# BEI_Kimco_Magnetic_Cylindrical_Frameless.net
KiCad netlist of a schematic drawn in EasyEDA Pro
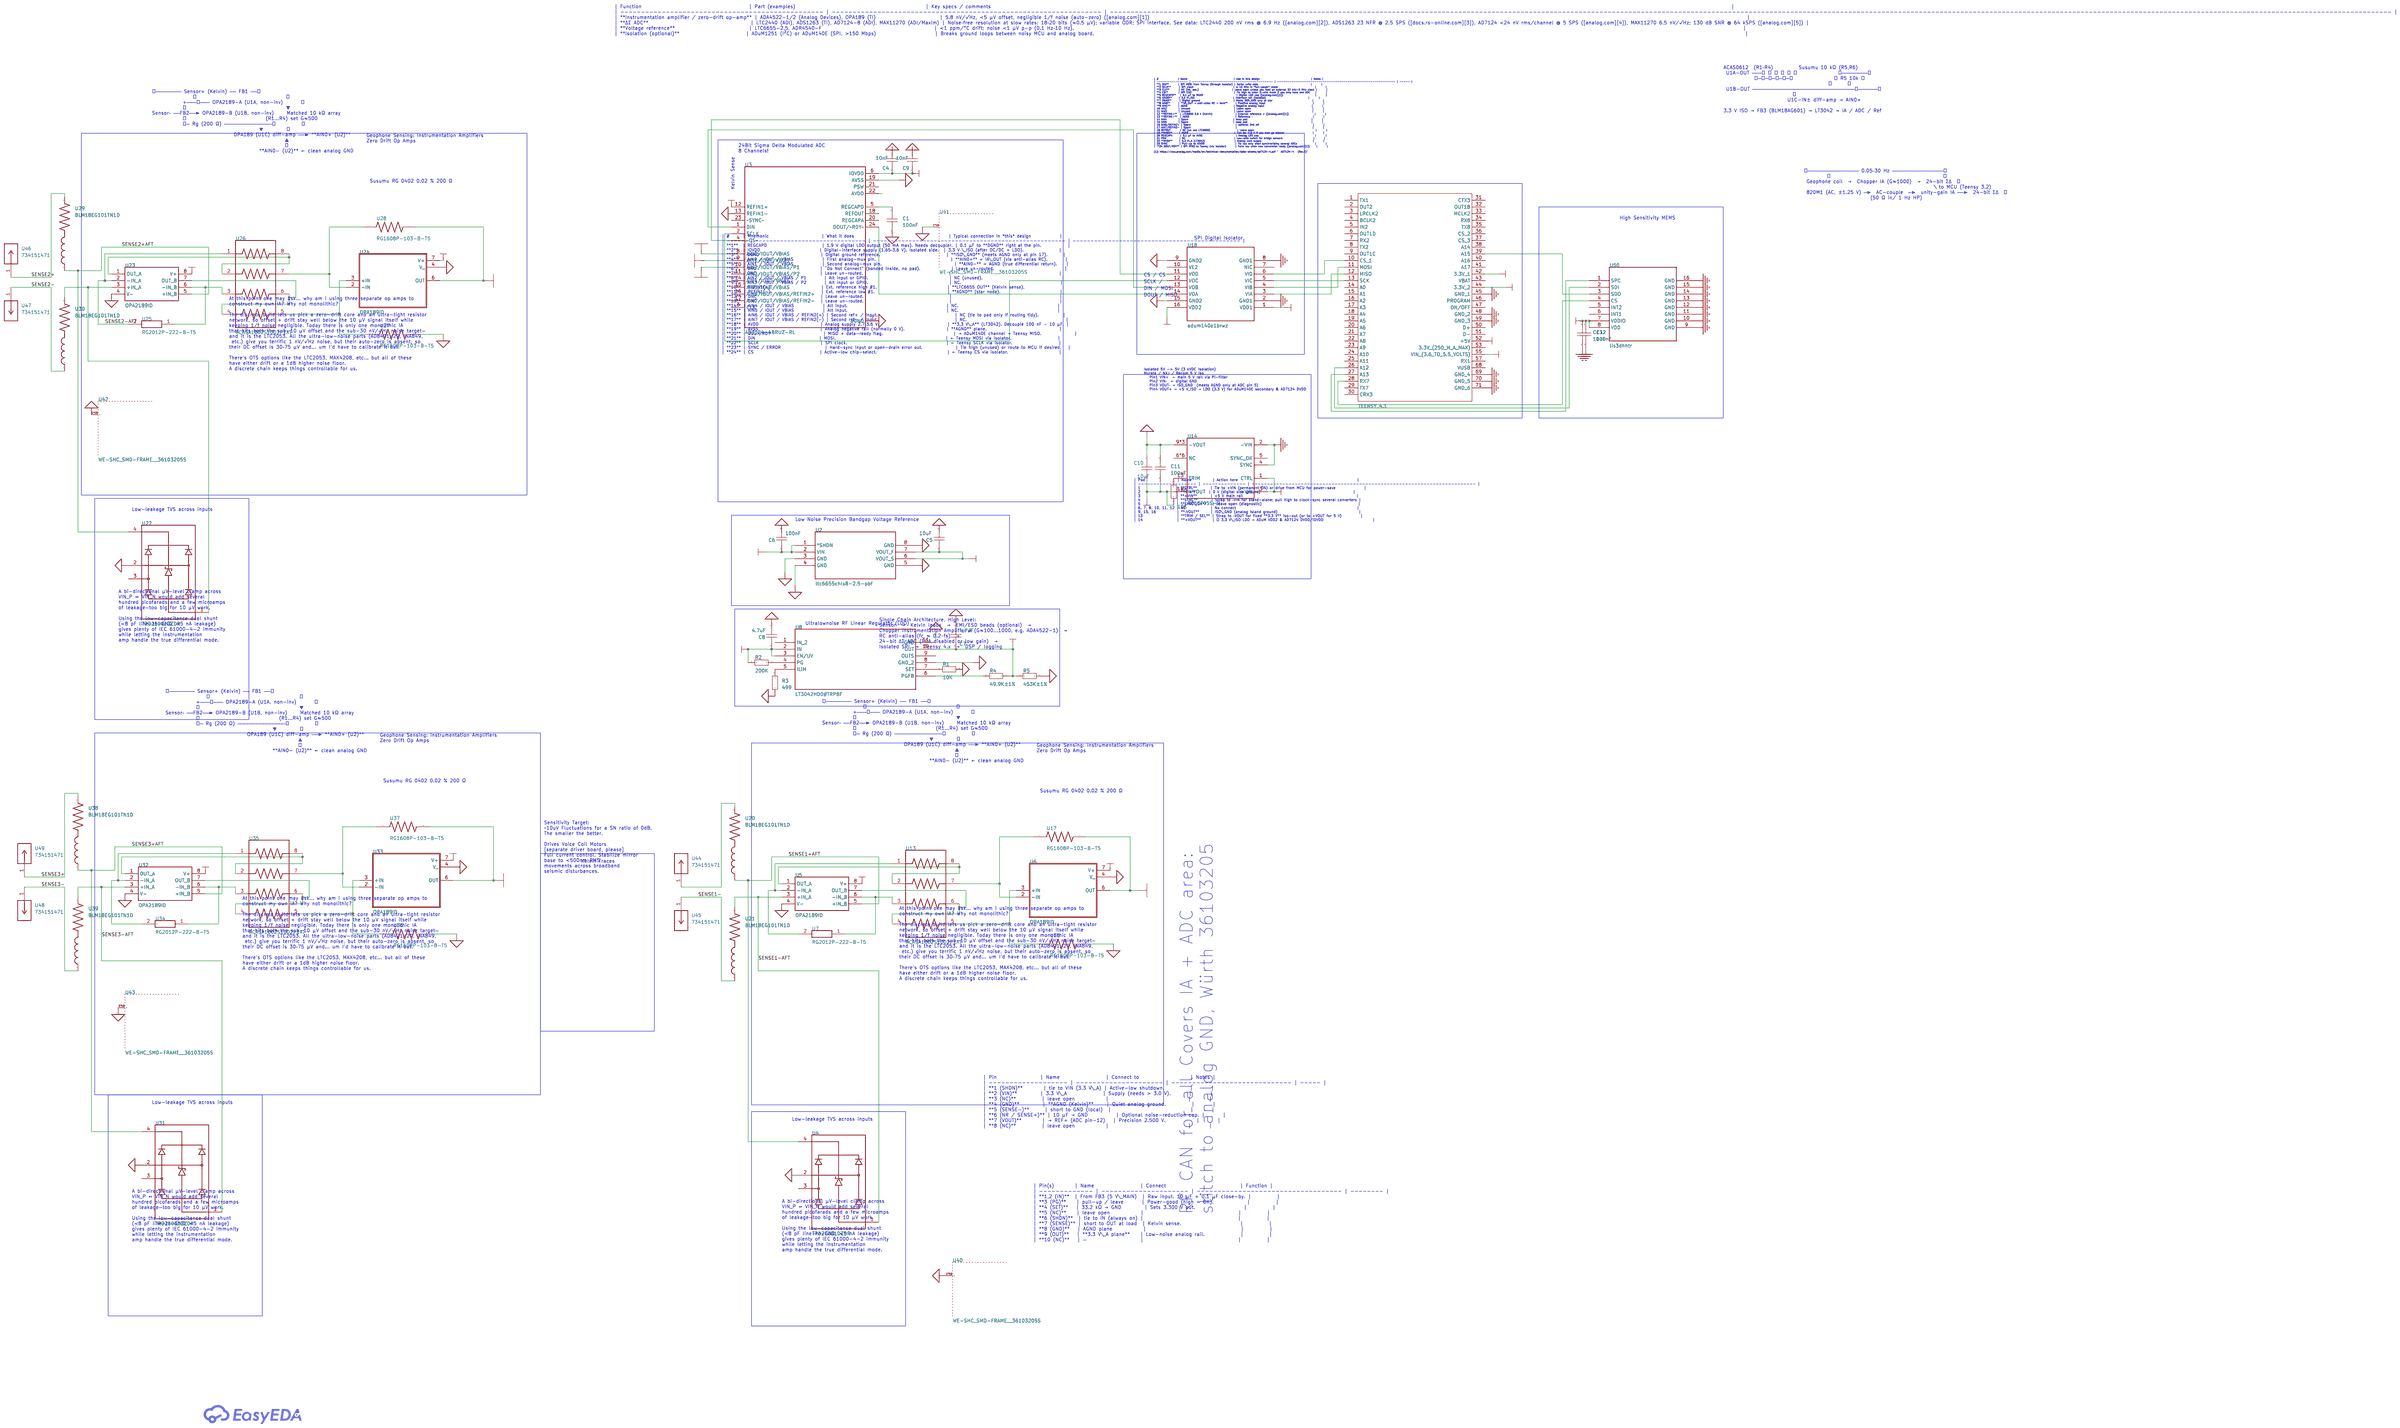
[diagram p0: schematic sheet]

(export (version "E")
  (design (tool "Eeschema 10.0.6"))
  (components
    (comp (ref "C1")
      (value "100nF")
      (footprint "easyedapro:C0603")
      (libsource (lib "easyedapro") (part "CapAcitance"))
    )
    (comp (ref "C4")
      (value "10nF")
      (footprint "easyedapro:C0603")
      (libsource (lib "easyedapro") (part "CapAcitance"))
    )
    (comp (ref "C5")
      (value "10uF")
      (footprint "easyedapro:C0603")
      (libsource (lib "easyedapro") (part "CapAcitance"))
    )
    (comp (ref "C6")
      (value "100nF")
      (footprint "easyedapro:C0603")
      (libsource (lib "easyedapro") (part "CapAcitance"))
    )
    (comp (ref "C7")
      (value "4.7uF")
      (footprint "easyedapro:C0603")
      (libsource (lib "easyedapro") (part "CapAcitance"))
    )
    (comp (ref "C8")
      (value "4.7uF")
      (footprint "easyedapro:C0603")
      (libsource (lib "easyedapro") (part "CapAcitance"))
    )
    (comp (ref "C9")
      (value "10nF")
      (footprint "easyedapro:C0603")
      (libsource (lib "easyedapro") (part "CapAcitance"))
    )
    (comp (ref "C10")
      (value "10uF")
      (footprint "easyedapro:C0603")
      (libsource (lib "easyedapro") (part "CapAcitance"))
    )
    (comp (ref "C11")
      (value "100nF")
      (footprint "easyedapro:C0603")
      (libsource (lib "easyedapro") (part "CapAcitance"))
    )
    (comp (ref "C12")
      (value "100nF")
      (footprint "easyedapro:C0603")
      (libsource (lib "easyedapro") (part "CapAcitance"))
    )
    (comp (ref "C13")
      (value "10uF")
      (footprint "easyedapro:C0603")
      (libsource (lib "easyedapro") (part "CapAcitance"))
    )
    (comp (ref "R1") (value "10K") (footprint "easyedapro:R0603") (libsource (lib "easyedapro") (part "电阻")))
    (comp (ref "R2") (value "200K") (footprint "easyedapro:R0603") (libsource (lib "easyedapro") (part "电阻")))
    (comp (ref "R3") (value "499") (footprint "easyedapro:R0603") (libsource (lib "easyedapro") (part "电阻")))
    (comp (ref "R4")
      (value "49.9K±1%")
      (footprint "easyedapro:R0603")
      (libsource (lib "easyedapro") (part "电阻"))
    )
    (comp (ref "R5")
      (value "453K±1%")
      (footprint "easyedapro:R0603")
      (libsource (lib "easyedapro") (part "电阻"))
    )
    (comp (ref "R6") (value "10K") (footprint "easyedapro:R0603") (libsource (lib "easyedapro") (part "电阻")))
    (comp (ref "U2")
      (value "ltc6655chls8-2.5-pbf")
      (footprint "easyedapro:LTC6655CHLS8-2.5-PBF")
      (libsource (lib "easyedapro") (part "ltc6655chls8-2.5-pbf"))
    )
    (comp (ref "U3")
      (value "AD7124-4BRUZ-RL")
      (footprint "easyedapro:SOP65P640X120-24N")
      (libsource (lib "easyedapro") (part "AD7124-4BRUZ-RL"))
    )
    (comp (ref "U4")
      (value "TPD2E001DZDR")
      (footprint "easyedapro:SOT192P237X122-4N")
      (libsource (lib "easyedapro") (part "TPD2E001DZDR"))
    )
    (comp (ref "U5")
      (value "OPA2189ID")
      (footprint "easyedapro:SOIC127P600X175-8N")
      (description "2 Op Amps in 1. Zero Drift.")
      (libsource (lib "easyedapro") (part "OPA2189ID"))
    )
    (comp (ref "U6")
      (value "OPA189ID")
      (footprint "easyedapro:SOIC127P599X175-8N")
      (libsource (lib "easyedapro") (part "OPA189ID"))
    )
    (comp (ref "U7")
      (value "RG2012P-222-B-T5")
      (footprint "easyedapro:RESC2012X50N")
      (libsource (lib "easyedapro") (part "RG2012P-222-B-T5"))
    )
    (comp (ref "U8")
      (value "LT3042HDD#TRPBF")
      (footprint "easyedapro:DFN-10_DD")
      (description "LDO")
      (libsource (lib "easyedapro") (part "LT3042HDD#TRPBF"))
    )
    (comp (ref "U13")
      (value "ACASA1002S1002P1AT")
      (footprint "easyedapro:RESCAXS80P320X150X55-8N")
      (libsource (lib "easyedapro") (part "ACASA1002S1002P1AT"))
    )
    (comp (ref "U14")
      (value "R05CT05S-R")
      (footprint "easyedapro:SOIC127P1030X265-16N")
      (description "Isolated 5 V→5 V DC/DC")
      (libsource (lib "easyedapro") (part "R05CT05S-R"))
    )
    (comp (ref "U16")
      (value "RG1608P-103-B-T5")
      (footprint "easyedapro:RESC1608X50N")
      (libsource (lib "easyedapro") (part "RG1608P-103-B-T5"))
    )
    (comp (ref "U17")
      (value "RG1608P-103-B-T5")
      (footprint "easyedapro:RESC1608X50N")
      (libsource (lib "easyedapro") (part "RG1608P-103-B-T5"))
    )
    (comp (ref "U18")
      (value "adum140e1brwz")
      (footprint "easyedapro:ADUM140E1BRWZ")
      (libsource (lib "easyedapro") (part "adum140e1brwz"))
    )
    (comp (ref "U20")
      (value "BLM18EG101TN1D")
      (footprint "easyedapro:BEADC1608X65N")
      (description "Ferrite Bead")
      (libsource (lib "easyedapro") (part "BLM18EG101TN1D"))
    )
    (comp (ref "U21")
      (value "BLM18EG101TN1D")
      (footprint "easyedapro:BEADC1608X65N")
      (description "Ferrite Bead")
      (libsource (lib "easyedapro") (part "BLM18EG101TN1D"))
    )
    (comp (ref "U22")
      (value "TPD2E001DZDR")
      (footprint "easyedapro:SOT192P237X122-4N")
      (libsource (lib "easyedapro") (part "TPD2E001DZDR"))
    )
    (comp (ref "U23")
      (value "OPA2189ID")
      (footprint "easyedapro:SOIC127P600X175-8N")
      (description "2 Op Amps in 1. Zero Drift.")
      (libsource (lib "easyedapro") (part "OPA2189ID"))
    )
    (comp (ref "U24")
      (value "OPA189ID")
      (footprint "easyedapro:SOIC127P599X175-8N")
      (libsource (lib "easyedapro") (part "OPA189ID"))
    )
    (comp (ref "U25")
      (value "RG2012P-222-B-T5")
      (footprint "easyedapro:RESC2012X50N")
      (libsource (lib "easyedapro") (part "RG2012P-222-B-T5"))
    )
    (comp (ref "U26")
      (value "ACASA1002S1002P1AT")
      (footprint "easyedapro:RESCAXS80P320X150X55-8N")
      (libsource (lib "easyedapro") (part "ACASA1002S1002P1AT"))
    )
    (comp (ref "U27")
      (value "RG1608P-103-B-T5")
      (footprint "easyedapro:RESC1608X50N")
      (libsource (lib "easyedapro") (part "RG1608P-103-B-T5"))
    )
    (comp (ref "U28")
      (value "RG1608P-103-B-T5")
      (footprint "easyedapro:RESC1608X50N")
      (libsource (lib "easyedapro") (part "RG1608P-103-B-T5"))
    )
    (comp (ref "U29")
      (value "BLM18EG101TN1D")
      (footprint "easyedapro:BEADC1608X65N")
      (description "Ferrite Bead")
      (libsource (lib "easyedapro") (part "BLM18EG101TN1D"))
    )
    (comp (ref "U30")
      (value "BLM18EG101TN1D")
      (footprint "easyedapro:BEADC1608X65N")
      (description "Ferrite Bead")
      (libsource (lib "easyedapro") (part "BLM18EG101TN1D"))
    )
    (comp (ref "U31")
      (value "TPD2E001DZDR")
      (footprint "easyedapro:SOT192P237X122-4N")
      (libsource (lib "easyedapro") (part "TPD2E001DZDR"))
    )
    (comp (ref "U32")
      (value "OPA2189ID")
      (footprint "easyedapro:SOIC127P600X175-8N")
      (description "2 Op Amps in 1. Zero Drift.")
      (libsource (lib "easyedapro") (part "OPA2189ID"))
    )
    (comp (ref "U33")
      (value "OPA189ID")
      (footprint "easyedapro:SOIC127P599X175-8N")
      (libsource (lib "easyedapro") (part "OPA189ID"))
    )
    (comp (ref "U34")
      (value "RG2012P-222-B-T5")
      (footprint "easyedapro:RESC2012X50N")
      (libsource (lib "easyedapro") (part "RG2012P-222-B-T5"))
    )
    (comp (ref "U35")
      (value "ACASA1002S1002P1AT")
      (footprint "easyedapro:RESCAXS80P320X150X55-8N")
      (libsource (lib "easyedapro") (part "ACASA1002S1002P1AT"))
    )
    (comp (ref "U36")
      (value "RG1608P-103-B-T5")
      (footprint "easyedapro:RESC1608X50N")
      (libsource (lib "easyedapro") (part "RG1608P-103-B-T5"))
    )
    (comp (ref "U37")
      (value "RG1608P-103-B-T5")
      (footprint "easyedapro:RESC1608X50N")
      (libsource (lib "easyedapro") (part "RG1608P-103-B-T5"))
    )
    (comp (ref "U38")
      (value "BLM18EG101TN1D")
      (footprint "easyedapro:BEADC1608X65N")
      (description "Ferrite Bead")
      (libsource (lib "easyedapro") (part "BLM18EG101TN1D"))
    )
    (comp (ref "U39")
      (value "BLM18EG101TN1D")
      (footprint "easyedapro:BEADC1608X65N")
      (description "Ferrite Bead")
      (libsource (lib "easyedapro") (part "BLM18EG101TN1D"))
    )
    (comp (ref "U40")
      (value "WE-SHC_SMD-FRAME__36103205S")
      (footprint "easyedapro:WE-SHC_SMD-FRAME_36103205S")
      (libsource (lib "easyedapro") (part "WE-SHC_SMD-FRAME__36103205S"))
    )
    (comp (ref "U41")
      (value "WE-SHC_SMD-FRAME__36103205S")
      (footprint "easyedapro:WE-SHC_SMD-FRAME_36103205S")
      (libsource (lib "easyedapro") (part "WE-SHC_SMD-FRAME__36103205S"))
    )
    (comp (ref "U42")
      (value "WE-SHC_SMD-FRAME__36103205S")
      (footprint "easyedapro:WE-SHC_SMD-FRAME_36103205S")
      (libsource (lib "easyedapro") (part "WE-SHC_SMD-FRAME__36103205S"))
    )
    (comp (ref "U43")
      (value "WE-SHC_SMD-FRAME__36103205S")
      (footprint "easyedapro:WE-SHC_SMD-FRAME_36103205S")
      (libsource (lib "easyedapro") (part "WE-SHC_SMD-FRAME__36103205S"))
    )
    (comp (ref "U44")
      (value "734151471")
      (footprint "easyedapro:CONN_734151471_MOL")
      (libsource (lib "easyedapro") (part "734151471"))
    )
    (comp (ref "U45")
      (value "734151471")
      (footprint "easyedapro:CONN_734151471_MOL")
      (libsource (lib "easyedapro") (part "734151471"))
    )
    (comp (ref "U46")
      (value "734151471")
      (footprint "easyedapro:CONN_734151471_MOL")
      (libsource (lib "easyedapro") (part "734151471"))
    )
    (comp (ref "U47")
      (value "734151471")
      (footprint "easyedapro:CONN_734151471_MOL")
      (libsource (lib "easyedapro") (part "734151471"))
    )
    (comp (ref "U48")
      (value "734151471")
      (footprint "easyedapro:CONN_734151471_MOL")
      (libsource (lib "easyedapro") (part "734151471"))
    )
    (comp (ref "U49")
      (value "734151471")
      (footprint "easyedapro:CONN_734151471_MOL")
      (libsource (lib "easyedapro") (part "734151471"))
    )
    (comp (ref "U50")
      (value "lis3dhhtr")
      (footprint "easyedapro:LIS3DHHTR")
      (libsource (lib "easyedapro") (part "lis3dhhtr"))
    )
    (comp (ref "U51")
      (value "TEENSY_4.1")
      (footprint "easyedapro:TEENSY41")
      (libsource (lib "easyedapro") (part "TEENSY_4.1"))
    )
  )
  (nets
    (net (code "1") (name "+2.5V") (class "Default")
      (node (ref "C5") (pin "2") (pinfunction "2_2") (pintype "input"))
      (node (ref "U2") (pin "6") (pinfunction "VOUT_S_6") (pintype "unspecified"))
      (node (ref "U2") (pin "7") (pinfunction "VOUT_F_7") (pintype "unspecified"))
      (node (ref "U3") (pin "12") (pinfunction "REFIN1+_12") (pintype "input"))
    )
    (net (code "2") (name "+3.3VANALOGSIDE") (class "Default")
      (node (ref "C4") (pin "1") (pinfunction "1_1") (pintype "input"))
      (node (ref "C6") (pin "2") (pinfunction "2_2") (pintype "input"))
      (node (ref "C7") (pin "2") (pinfunction "2_2") (pintype "input"))
      (node (ref "C9") (pin "1") (pinfunction "1_1") (pintype "input"))
      (node (ref "R4") (pin "2") (pinfunction "2_2") (pintype "input"))
      (node (ref "R5") (pin "1") (pinfunction "1_1") (pintype "input"))
      (node (ref "U18") (pin "16") (pinfunction "VDD2_16") (pintype "unspecified"))
      (node (ref "U2") (pin "1") (pinfunction "*SHDN_1") (pintype "unspecified"))
      (node (ref "U2") (pin "2") (pinfunction "VIN_2") (pintype "unspecified"))
      (node (ref "U23") (pin "8") (pinfunction "V+_8") (pintype "bidirectional"))
      (node (ref "U24") (pin "7") (pinfunction "V+_7") (pintype "unspecified"))
      (node (ref "U3") (pin "6") (pinfunction "IOVDD_6") (pintype "unspecified"))
      (node (ref "U32") (pin "8") (pinfunction "V+_8") (pintype "bidirectional"))
      (node (ref "U33") (pin "7") (pinfunction "V+_7") (pintype "unspecified"))
      (node (ref "U5") (pin "8") (pinfunction "V+_8") (pintype "bidirectional"))
      (node (ref "U6") (pin "7") (pinfunction "V+_7") (pintype "unspecified"))
      (node (ref "U8") (pin "10") (pinfunction "OUT_10") (pintype "output"))
    )
    (net (code "3") (name "+3.3V_D") (class "Default")
      (node (ref "C12") (pin "2") (pinfunction "2_2") (pintype "input"))
      (node (ref "C13") (pin "2") (pinfunction "2_2") (pintype "input"))
      (node (ref "U18") (pin "1") (pinfunction "VDD1_1") (pintype "unspecified"))
      (node (ref "U50") (pin "7") (pinfunction "VDDIO_7") (pintype "unspecified"))
      (node (ref "U50") (pin "8") (pinfunction "VDD_8") (pintype "unspecified"))
      (node (ref "U51") (pin "42") (pinfunction "3.3V_1_42") (pintype "bidirectional"))
      (node (ref "U51") (pin "44") (pinfunction "3.3V_2_44") (pintype "bidirectional"))
    )
    (net (code "4") (name "+5V_D") (class "Default")
      (node (ref "U14") (pin "1") (pinfunction "CTRL_1") (pintype "input"))
      (node (ref "U14") (pin "3") (pinfunction "+VIN_3") (pintype "input"))
      (node (ref "U51") (pin "52") (pinfunction "+5V_52") (pintype "bidirectional"))
      (node (ref "U51") (pin "55") (pinfunction "VIN_(3.6_TO_5.5_VOLTS)_55") (pintype "bidirectional"))
    )
    (net (code "5") (name "+5V_ISO") (class "Default")
      (node (ref "C10") (pin "1") (pinfunction "1_1") (pintype "input"))
      (node (ref "C11") (pin "1") (pinfunction "1_1") (pintype "input"))
      (node (ref "C8") (pin "2") (pinfunction "2_2") (pintype "input"))
      (node (ref "R2") (pin "1") (pinfunction "1_1") (pintype "input"))
      (node (ref "R6") (pin "1") (pinfunction "1_1") (pintype "input"))
      (node (ref "U14") (pin "14") (pinfunction "+VOUT_14") (pintype "output"))
      (node (ref "U8") (pin "2") (pinfunction "IN_2") (pintype "input"))
      (node (ref "U8") (pin "3") (pinfunction "EN/UV_3") (pintype "output"))
    )
    (net (code "6") (name "/SENSE1+AFT") (class "Default")
      (node (ref "U20") (pin "1") (pinfunction "1_1") (pintype "unspecified"))
      (node (ref "U4") (pin "4") (pinfunction "VCC_4") (pintype "unspecified"))
      (node (ref "U5") (pin "5") (pinfunction "+IN_B_5") (pintype "bidirectional"))
    )
    (net (code "7") (name "/SENSE1-") (class "Default")
      (node (ref "U21") (pin "1") (pinfunction "1_1") (pintype "unspecified"))
      (node (ref "U45") (pin "1") (pinfunction "1_1") (pintype "unspecified"))
    )
    (net (code "8") (name "/SENSE1-AFT") (class "Default")
      (node (ref "U21") (pin "2") (pinfunction "2_2") (pintype "unspecified"))
      (node (ref "U4") (pin "1") (pinfunction "GND_1") (pintype "unspecified"))
      (node (ref "U5") (pin "3") (pinfunction "+IN_A_3") (pintype "bidirectional"))
    )
    (net (code "9") (name "/SENSE2+") (class "Default")
      (node (ref "U29") (pin "2") (pinfunction "2_2") (pintype "unspecified"))
      (node (ref "U46") (pin "1") (pinfunction "1_1") (pintype "unspecified"))
    )
    (net (code "10") (name "/SENSE2+AFT") (class "Default")
      (node (ref "U22") (pin "4") (pinfunction "VCC_4") (pintype "unspecified"))
      (node (ref "U23") (pin "5") (pinfunction "+IN_B_5") (pintype "bidirectional"))
      (node (ref "U29") (pin "1") (pinfunction "1_1") (pintype "unspecified"))
    )
    (net (code "11") (name "/SENSE2-") (class "Default")
      (node (ref "U30") (pin "1") (pinfunction "1_1") (pintype "unspecified"))
      (node (ref "U47") (pin "1") (pinfunction "1_1") (pintype "unspecified"))
    )
    (net (code "12") (name "/SENSE2-AFT") (class "Default")
      (node (ref "U23") (pin "2") (pinfunction "-IN_A_2") (pintype "bidirectional"))
      (node (ref "U25") (pin "2") (pinfunction "2_2") (pintype "bidirectional"))
      (node (ref "U26") (pin "1") (pinfunction "1_1") (pintype "unspecified"))
    )
    (net (code "13") (name "/SENSE3+") (class "Default")
      (node (ref "U38") (pin "2") (pinfunction "2_2") (pintype "unspecified"))
      (node (ref "U49") (pin "1") (pinfunction "1_1") (pintype "unspecified"))
    )
    (net (code "14") (name "/SENSE3+AFT") (class "Default")
      (node (ref "U31") (pin "4") (pinfunction "VCC_4") (pintype "unspecified"))
      (node (ref "U32") (pin "5") (pinfunction "+IN_B_5") (pintype "bidirectional"))
      (node (ref "U38") (pin "1") (pinfunction "1_1") (pintype "unspecified"))
    )
    (net (code "15") (name "/SENSE3-") (class "Default")
      (node (ref "U39") (pin "1") (pinfunction "1_1") (pintype "unspecified"))
      (node (ref "U48") (pin "1") (pinfunction "1_1") (pintype "unspecified"))
    )
    (net (code "16") (name "/SENSE3-AFT") (class "Default")
      (node (ref "U31") (pin "1") (pinfunction "GND_1") (pintype "unspecified"))
      (node (ref "U32") (pin "3") (pinfunction "+IN_A_3") (pintype "bidirectional"))
      (node (ref "U39") (pin "2") (pinfunction "2_2") (pintype "unspecified"))
    )
    (net (code "17") (name "AGND") (class "Default")
      (node (ref "C1") (pin "2") (pinfunction "2_2") (pintype "input"))
      (node (ref "C10") (pin "2") (pinfunction "2_2") (pintype "input"))
      (node (ref "C11") (pin "2") (pinfunction "2_2") (pintype "input"))
      (node (ref "C4") (pin "2") (pinfunction "2_2") (pintype "input"))
      (node (ref "C5") (pin "1") (pinfunction "1_1") (pintype "input"))
      (node (ref "C6") (pin "1") (pinfunction "1_1") (pintype "input"))
      (node (ref "C7") (pin "1") (pinfunction "1_1") (pintype "input"))
      (node (ref "C8") (pin "1") (pinfunction "1_1") (pintype "input"))
      (node (ref "C9") (pin "2") (pinfunction "2_2") (pintype "input"))
      (node (ref "R1") (pin "2") (pinfunction "2_2") (pintype "input"))
      (node (ref "R3") (pin "1") (pinfunction "1_1") (pintype "input"))
      (node (ref "R5") (pin "2") (pinfunction "2_2") (pintype "input"))
      (node (ref "U14") (pin "9*3") (pinfunction "-VOUT_9*3") (pintype "output"))
      (node (ref "U16") (pin "2") (pinfunction "2_2") (pintype "unspecified"))
      (node (ref "U18") (pin "15") (pinfunction "GND2_15") (pintype "unspecified"))
      (node (ref "U18") (pin "9") (pinfunction "GND2_9") (pintype "unspecified"))
      (node (ref "U2") (pin "3") (pinfunction "GND_3") (pintype "unspecified"))
      (node (ref "U2") (pin "4") (pinfunction "GND_4") (pintype "unspecified"))
      (node (ref "U2") (pin "5") (pinfunction "GND_5") (pintype "unspecified"))
      (node (ref "U2") (pin "8") (pinfunction "GND_8") (pintype "unspecified"))
      (node (ref "U22") (pin "2") (pinfunction "IO1_2") (pintype "bidirectional"))
      (node (ref "U23") (pin "4") (pinfunction "V-_4") (pintype "bidirectional"))
      (node (ref "U24") (pin "4") (pinfunction "V__4") (pintype "unspecified"))
      (node (ref "U27") (pin "2") (pinfunction "2_2") (pintype "unspecified"))
      (node (ref "U3") (pin "13") (pinfunction "REFIN1-_13") (pintype "input"))
      (node (ref "U3") (pin "19") (pinfunction "AVSS_19") (pintype "unspecified"))
      (node (ref "U3") (pin "7") (pinfunction "DGND_7") (pintype "unspecified"))
      (node (ref "U31") (pin "2") (pinfunction "IO1_2") (pintype "bidirectional"))
      (node (ref "U32") (pin "4") (pinfunction "V-_4") (pintype "bidirectional"))
      (node (ref "U33") (pin "4") (pinfunction "V__4") (pintype "unspecified"))
      (node (ref "U36") (pin "2") (pinfunction "2_2") (pintype "unspecified"))
      (node (ref "U4") (pin "2") (pinfunction "IO1_2") (pintype "bidirectional"))
      (node (ref "U40") (pin "1*16") (pinfunction "GND_1*16") (pintype "unspecified"))
      (node (ref "U41") (pin "1*16") (pinfunction "GND_1*16") (pintype "unspecified"))
      (node (ref "U42") (pin "1*16") (pinfunction "GND_1*16") (pintype "unspecified"))
      (node (ref "U43") (pin "1*16") (pinfunction "GND_1*16") (pintype "unspecified"))
      (node (ref "U5") (pin "4") (pinfunction "V-_4") (pintype "bidirectional"))
      (node (ref "U6") (pin "4") (pinfunction "V__4") (pintype "unspecified"))
      (node (ref "U8") (pin "11") (pinfunction "GND_11") (pintype "unspecified"))
      (node (ref "U8") (pin "8") (pinfunction "GND_2_8") (pintype "unspecified"))
    )
    (net (code "18") (name "DGND") (class "Default")
      (node (ref "C12") (pin "1") (pinfunction "1_1") (pintype "input"))
      (node (ref "C13") (pin "1") (pinfunction "1_1") (pintype "input"))
      (node (ref "U14") (pin "2") (pinfunction "-VIN_2") (pintype "input"))
      (node (ref "U14") (pin "4") (pinfunction "SYNC_4") (pintype "input"))
      (node (ref "U18") (pin "2") (pinfunction "GND1_2") (pintype "unspecified"))
      (node (ref "U18") (pin "8") (pinfunction "GND1_8") (pintype "unspecified"))
      (node (ref "U50") (pin "10") (pinfunction "GND_10") (pintype "unspecified"))
      (node (ref "U50") (pin "11") (pinfunction "GND_11") (pintype "unspecified"))
      (node (ref "U50") (pin "12") (pinfunction "GND_12") (pintype "unspecified"))
      (node (ref "U50") (pin "13") (pinfunction "GND_13") (pintype "unspecified"))
      (node (ref "U50") (pin "14") (pinfunction "GND_14") (pintype "unspecified"))
      (node (ref "U50") (pin "15") (pinfunction "GND_15") (pintype "unspecified"))
      (node (ref "U50") (pin "16") (pinfunction "GND_16") (pintype "unspecified"))
      (node (ref "U50") (pin "9") (pinfunction "GND_9") (pintype "unspecified"))
      (node (ref "U51") (pin "45") (pinfunction "GND_1_45") (pintype "bidirectional"))
      (node (ref "U51") (pin "48") (pinfunction "GND_2_48") (pintype "bidirectional"))
      (node (ref "U51") (pin "49") (pinfunction "GND_3_49") (pintype "bidirectional"))
      (node (ref "U51") (pin "69") (pinfunction "GND_4_69") (pintype "bidirectional"))
      (node (ref "U51") (pin "70") (pinfunction "GND_5_70") (pintype "bidirectional"))
      (node (ref "U51") (pin "71") (pinfunction "GND_6_71") (pintype "bidirectional"))
    )
    (net (code "19") (name "Net-(U3-REGCAPD)") (class "Default")
      (node (ref "C1") (pin "1") (pinfunction "1_1") (pintype "input"))
      (node (ref "U3") (pin "5") (pinfunction "REGCAPD_5") (pintype "output"))
    )
    (net (code "20") (name "Net-(U5--IN_A)") (class "Default")
      (node (ref "U13") (pin "1") (pinfunction "1_1") (pintype "unspecified"))
      (node (ref "U5") (pin "2") (pinfunction "-IN_A_2") (pintype "bidirectional"))
      (node (ref "U7") (pin "2") (pinfunction "2_2") (pintype "bidirectional"))
    )
    (net (code "21") (name "Net-(U5--IN_B)") (class "Default")
      (node (ref "U13") (pin "3") (pinfunction "3_3") (pintype "unspecified"))
      (node (ref "U5") (pin "6") (pinfunction "-IN_B_6") (pintype "bidirectional"))
      (node (ref "U7") (pin "1") (pinfunction "1_1") (pintype "bidirectional"))
    )
    (net (code "22") (name "Net-(U5-OUT_A)") (class "Default")
      (node (ref "U13") (pin "2") (pinfunction "2_2") (pintype "unspecified"))
      (node (ref "U13") (pin "8") (pinfunction "8_8") (pintype "unspecified"))
      (node (ref "U5") (pin "1") (pinfunction "OUT_A_1") (pintype "bidirectional"))
    )
    (net (code "23") (name "Net-(U5-OUT_B)") (class "Default")
      (node (ref "U13") (pin "4") (pinfunction "4_4") (pintype "unspecified"))
      (node (ref "U13") (pin "6") (pinfunction "6_6") (pintype "unspecified"))
      (node (ref "U5") (pin "7") (pinfunction "OUT_B_7") (pintype "bidirectional"))
    )
    (net (code "24") (name "Net-(U6-+IN)") (class "Default")
      (node (ref "U13") (pin "5") (pinfunction "5_5") (pintype "unspecified"))
      (node (ref "U16") (pin "1") (pinfunction "1_1") (pintype "unspecified"))
      (node (ref "U6") (pin "3") (pinfunction "+IN_3") (pintype "input"))
    )
    (net (code "25") (name "Net-(U6--IN)") (class "Default")
      (node (ref "U13") (pin "7") (pinfunction "7_7") (pintype "unspecified"))
      (node (ref "U17") (pin "1") (pinfunction "1_1") (pintype "unspecified"))
      (node (ref "U6") (pin "2") (pinfunction "-IN_2") (pintype "input"))
    )
    (net (code "26") (name "Net-(U8-ILIM)") (class "Default")
      (node (ref "R3") (pin "2") (pinfunction "2_2") (pintype "input"))
      (node (ref "U8") (pin "5") (pinfunction "ILIM_5") (pintype "unspecified"))
    )
    (net (code "27") (name "Net-(U8-PG)") (class "Default")
      (node (ref "R2") (pin "2") (pinfunction "2_2") (pintype "input"))
      (node (ref "U8") (pin "4") (pinfunction "PG_4") (pintype "unspecified"))
    )
    (net (code "28") (name "Net-(U8-PGFB)") (class "Default")
      (node (ref "R4") (pin "1") (pinfunction "1_1") (pintype "input"))
      (node (ref "U8") (pin "6") (pinfunction "PGFB_6") (pintype "unspecified"))
    )
    (net (code "29") (name "Net-(U8-SET)") (class "Default")
      (node (ref "R1") (pin "1") (pinfunction "1_1") (pintype "input"))
      (node (ref "U8") (pin "7") (pinfunction "SET_7") (pintype "input"))
    )
    (net (code "30") (name "Net-(U14-TRIM)") (class "Default")
      (node (ref "R6") (pin "2") (pinfunction "2_2") (pintype "input"))
      (node (ref "U14") (pin "13") (pinfunction "TRIM_13") (pintype "unspecified"))
    )
    (net (code "31") (name "Net-(U18-VIA)") (class "Default")
      (node (ref "U18") (pin "3") (pinfunction "VIA_3") (pintype "unspecified"))
      (node (ref "U51") (pin "12") (pinfunction "MISO_12") (pintype "bidirectional"))
    )
    (net (code "32") (name "Net-(U18-VIB)") (class "Default")
      (node (ref "U18") (pin "4") (pinfunction "VIB_4") (pintype "unspecified"))
      (node (ref "U51") (pin "11") (pinfunction "MOSI_11") (pintype "bidirectional"))
    )
    (net (code "33") (name "Net-(U18-VIC)") (class "Default")
      (node (ref "U18") (pin "5") (pinfunction "VIC_5") (pintype "unspecified"))
      (node (ref "U51") (pin "13") (pinfunction "SCK_13") (pintype "bidirectional"))
    )
    (net (code "34") (name "Net-(U18-VID)") (class "Default")
      (node (ref "U18") (pin "6") (pinfunction "VID_6") (pintype "unspecified"))
      (node (ref "U51") (pin "10") (pinfunction "CS_1_10") (pintype "bidirectional"))
    )
    (net (code "35") (name "Net-(U18-VOA)") (class "Default")
      (node (ref "U18") (pin "14") (pinfunction "VOA_14") (pintype "unspecified"))
      (node (ref "U3") (pin "24") (pinfunction "DOUT/~RDY~_24") (pintype "output"))
    )
    (net (code "36") (name "Net-(U18-VOB)") (class "Default")
      (node (ref "U18") (pin "13") (pinfunction "VOB_13") (pintype "unspecified"))
      (node (ref "U3") (pin "1") (pinfunction "DIN_1") (pintype "input"))
    )
    (net (code "37") (name "Net-(U18-VOC)") (class "Default")
      (node (ref "U18") (pin "12") (pinfunction "VOC_12") (pintype "unspecified"))
      (node (ref "U3") (pin "2") (pinfunction "SCLK_2") (pintype "input"))
    )
    (net (code "38") (name "Net-(U18-VOD)") (class "Default")
      (node (ref "U18") (pin "11") (pinfunction "VOD_11") (pintype "unspecified"))
      (node (ref "U3") (pin "4") (pinfunction "~CS~_4") (pintype "input"))
    )
    (net (code "39") (name "Net-(U20-Pad2)") (class "Default")
      (node (ref "U20") (pin "2") (pinfunction "2_2") (pintype "unspecified"))
      (node (ref "U44") (pin "1") (pinfunction "1_1") (pintype "unspecified"))
    )
    (net (code "40") (name "Net-(U22-GND)") (class "Default")
      (node (ref "U22") (pin "1") (pinfunction "GND_1") (pintype "unspecified"))
      (node (ref "U23") (pin "3") (pinfunction "+IN_A_3") (pintype "bidirectional"))
      (node (ref "U30") (pin "2") (pinfunction "2_2") (pintype "unspecified"))
    )
    (net (code "41") (name "Net-(U23--IN_B)") (class "Default")
      (node (ref "U23") (pin "6") (pinfunction "-IN_B_6") (pintype "bidirectional"))
      (node (ref "U25") (pin "1") (pinfunction "1_1") (pintype "bidirectional"))
      (node (ref "U26") (pin "3") (pinfunction "3_3") (pintype "unspecified"))
    )
    (net (code "42") (name "Net-(U23-OUT_A)") (class "Default")
      (node (ref "U23") (pin "1") (pinfunction "OUT_A_1") (pintype "bidirectional"))
      (node (ref "U26") (pin "2") (pinfunction "2_2") (pintype "unspecified"))
      (node (ref "U26") (pin "8") (pinfunction "8_8") (pintype "unspecified"))
    )
    (net (code "43") (name "Net-(U23-OUT_B)") (class "Default")
      (node (ref "U23") (pin "7") (pinfunction "OUT_B_7") (pintype "bidirectional"))
      (node (ref "U26") (pin "4") (pinfunction "4_4") (pintype "unspecified"))
      (node (ref "U26") (pin "6") (pinfunction "6_6") (pintype "unspecified"))
    )
    (net (code "44") (name "Net-(U24-+IN)") (class "Default")
      (node (ref "U24") (pin "3") (pinfunction "+IN_3") (pintype "input"))
      (node (ref "U26") (pin "5") (pinfunction "5_5") (pintype "unspecified"))
      (node (ref "U27") (pin "1") (pinfunction "1_1") (pintype "unspecified"))
    )
    (net (code "45") (name "Net-(U24--IN)") (class "Default")
      (node (ref "U24") (pin "2") (pinfunction "-IN_2") (pintype "input"))
      (node (ref "U26") (pin "7") (pinfunction "7_7") (pintype "unspecified"))
      (node (ref "U28") (pin "1") (pinfunction "1_1") (pintype "unspecified"))
    )
    (net (code "46") (name "Net-(U32--IN_A)") (class "Default")
      (node (ref "U32") (pin "2") (pinfunction "-IN_A_2") (pintype "bidirectional"))
      (node (ref "U34") (pin "2") (pinfunction "2_2") (pintype "bidirectional"))
      (node (ref "U35") (pin "1") (pinfunction "1_1") (pintype "unspecified"))
    )
    (net (code "47") (name "Net-(U32--IN_B)") (class "Default")
      (node (ref "U32") (pin "6") (pinfunction "-IN_B_6") (pintype "bidirectional"))
      (node (ref "U34") (pin "1") (pinfunction "1_1") (pintype "bidirectional"))
      (node (ref "U35") (pin "3") (pinfunction "3_3") (pintype "unspecified"))
    )
    (net (code "48") (name "Net-(U32-OUT_A)") (class "Default")
      (node (ref "U32") (pin "1") (pinfunction "OUT_A_1") (pintype "bidirectional"))
      (node (ref "U35") (pin "2") (pinfunction "2_2") (pintype "unspecified"))
      (node (ref "U35") (pin "8") (pinfunction "8_8") (pintype "unspecified"))
    )
    (net (code "49") (name "Net-(U32-OUT_B)") (class "Default")
      (node (ref "U32") (pin "7") (pinfunction "OUT_B_7") (pintype "bidirectional"))
      (node (ref "U35") (pin "4") (pinfunction "4_4") (pintype "unspecified"))
      (node (ref "U35") (pin "6") (pinfunction "6_6") (pintype "unspecified"))
    )
    (net (code "50") (name "Net-(U33-+IN)") (class "Default")
      (node (ref "U33") (pin "3") (pinfunction "+IN_3") (pintype "input"))
      (node (ref "U35") (pin "5") (pinfunction "5_5") (pintype "unspecified"))
      (node (ref "U36") (pin "1") (pinfunction "1_1") (pintype "unspecified"))
    )
    (net (code "51") (name "Net-(U33--IN)") (class "Default")
      (node (ref "U33") (pin "2") (pinfunction "-IN_2") (pintype "input"))
      (node (ref "U35") (pin "7") (pinfunction "7_7") (pintype "unspecified"))
      (node (ref "U37") (pin "1") (pinfunction "1_1") (pintype "unspecified"))
    )
    (net (code "52") (name "Net-(U50-CS)") (class "Default")
      (node (ref "U50") (pin "4") (pinfunction "CS_4") (pintype "unspecified"))
      (node (ref "U51") (pin "28") (pinfunction "RX7_28") (pintype "bidirectional"))
    )
    (net (code "53") (name "Net-(U50-SDI)") (class "Default")
      (node (ref "U50") (pin "2") (pinfunction "SDI_2") (pintype "unspecified"))
      (node (ref "U51") (pin "26") (pinfunction "A12_26") (pintype "bidirectional"))
    )
    (net (code "54") (name "Net-(U50-SDO)") (class "Default")
      (node (ref "U50") (pin "3") (pinfunction "SDO_3") (pintype "unspecified"))
      (node (ref "U51") (pin "39") (pinfunction "A15_39") (pintype "bidirectional"))
    )
    (net (code "55") (name "Net-(U50-SPC)") (class "Default")
      (node (ref "U50") (pin "1") (pinfunction "SPC_1") (pintype "unspecified"))
      (node (ref "U51") (pin "27") (pinfunction "A13_27") (pintype "bidirectional"))
    )
    (net (code "56") (name "VOUT1") (class "Default")
      (node (ref "U17") (pin "2") (pinfunction "2_2") (pintype "unspecified"))
      (node (ref "U3") (pin "8") (pinfunction "AIN0/IOUT/VBIAS_8") (pintype "bidirectional"))
      (node (ref "U6") (pin "6") (pinfunction "OUT_6") (pintype "output"))
    )
    (net (code "57") (name "VOUT2") (class "Default")
      (node (ref "U24") (pin "6") (pinfunction "OUT_6") (pintype "output"))
      (node (ref "U28") (pin "2") (pinfunction "2_2") (pintype "unspecified"))
      (node (ref "U3") (pin "9") (pinfunction "AIN1/IOUT/VBIAS_9") (pintype "bidirectional"))
    )
    (net (code "58") (name "VOUT3") (class "Default")
      (node (ref "U3") (pin "10") (pinfunction "AIN2/IOUT/VBIAS/P1_10") (pintype "bidirectional"))
      (node (ref "U33") (pin "6") (pinfunction "OUT_6") (pintype "output"))
      (node (ref "U37") (pin "2") (pinfunction "2_2") (pintype "unspecified"))
    )
    (net (code "59") (name "unconnected-(U3-AIN3{slash}IOUT{slash}VBIAS{slash}P2-Pad11)") (class "Default")
      (node (ref "U3") (pin "11") (pinfunction "AIN3/IOUT/VBIAS/P2_11") (pintype "bidirectional"))
    )
    (net (code "60") (name "unconnected-(U3-AIN4{slash}IOUT{slash}VBIAS-Pad14)") (class "Default")
      (node (ref "U3") (pin "14") (pinfunction "AIN4/IOUT/VBIAS_14") (pintype "bidirectional"))
    )
    (net (code "61") (name "unconnected-(U3-AIN5{slash}IOUT{slash}VBIAS-Pad15)") (class "Default")
      (node (ref "U3") (pin "15") (pinfunction "AIN5/IOUT/VBIAS_15") (pintype "bidirectional"))
    )
    (net (code "62") (name "unconnected-(U3-AIN6{slash}IOUT{slash}VBIAS{slash}REFIN2+-Pad16)") (class "Default")
      (node (ref "U3") (pin "16") (pinfunction "AIN6/IOUT/VBIAS/REFIN2+_16") (pintype "bidirectional"))
    )
    (net (code "63") (name "unconnected-(U3-AIN7{slash}IOUT{slash}VBIAS{slash}REFIN2--Pad17)") (class "Default")
      (node (ref "U3") (pin "17") (pinfunction "AIN7/IOUT/VBIAS/REFIN2-_17") (pintype "bidirectional"))
    )
    (net (code "64") (name "unconnected-(U3-AVDD-Pad22)") (class "Default")
      (node (ref "U3") (pin "22") (pinfunction "AVDD_22") (pintype "unspecified"))
    )
    (net (code "65") (name "unconnected-(U3-CLK-Pad3)") (class "Default")
      (node (ref "U3") (pin "3") (pinfunction "CLK_3") (pintype "bidirectional"))
    )
    (net (code "66") (name "unconnected-(U3-PSW-Pad21)") (class "Default")
      (node (ref "U3") (pin "21") (pinfunction "PSW_21") (pintype "unspecified"))
    )
    (net (code "67") (name "unconnected-(U3-REFOUT-Pad18)") (class "Default")
      (node (ref "U3") (pin "18") (pinfunction "REFOUT_18") (pintype "output"))
    )
    (net (code "68") (name "unconnected-(U3-REGCAPA-Pad20)") (class "Default")
      (node (ref "U3") (pin "20") (pinfunction "REGCAPA_20") (pintype "output"))
    )
    (net (code "69") (name "unconnected-(U3-~SYNC~-Pad23)") (class "Default")
      (node (ref "U3") (pin "23") (pinfunction "~SYNC~_23") (pintype "input"))
    )
    (net (code "70") (name "unconnected-(U4-IO2-Pad3)") (class "Default")
      (node (ref "U4") (pin "3") (pinfunction "IO2_3") (pintype "bidirectional"))
    )
    (net (code "71") (name "unconnected-(U8-IN_2-Pad1)") (class "Default")
      (node (ref "U8") (pin "1") (pinfunction "IN_2_1") (pintype "input"))
    )
    (net (code "72") (name "unconnected-(U8-OUTS-Pad9)") (class "Default")
      (node (ref "U8") (pin "9") (pinfunction "OUTS_9") (pintype "output"))
    )
    (net (code "73") (name "unconnected-(U14-NC-Pad6*6)") (class "Default")
      (node (ref "U14") (pin "6*6") (pinfunction "NC_6*6") (pintype "unspecified"))
    )
    (net (code "74") (name "unconnected-(U14-SYNC_OK-Pad5)") (class "Default")
      (node (ref "U14") (pin "5") (pinfunction "SYNC_OK_5") (pintype "input"))
    )
    (net (code "75") (name "unconnected-(U18-NIC-Pad7)") (class "Default")
      (node (ref "U18") (pin "7") (pinfunction "NIC_7") (pintype "unspecified"))
    )
    (net (code "76") (name "unconnected-(U18-VE2-Pad10)") (class "Default")
      (node (ref "U18") (pin "10") (pinfunction "VE2_10") (pintype "unspecified"))
    )
    (net (code "77") (name "unconnected-(U22-IO2-Pad3)") (class "Default")
      (node (ref "U22") (pin "3") (pinfunction "IO2_3") (pintype "bidirectional"))
    )
    (net (code "78") (name "unconnected-(U31-IO2-Pad3)") (class "Default")
      (node (ref "U31") (pin "3") (pinfunction "IO2_3") (pintype "bidirectional"))
    )
    (net (code "79") (name "unconnected-(U50-INT1-Pad6)") (class "Default")
      (node (ref "U50") (pin "6") (pinfunction "INT1_6") (pintype "unspecified"))
    )
    (net (code "80") (name "unconnected-(U50-INT2-Pad5)") (class "Default")
      (node (ref "U50") (pin "5") (pinfunction "INT2_5") (pintype "unspecified"))
    )
    (net (code "81") (name "unconnected-(U51-3.3V_(250_M_A_MAX)-Pad53)") (class "Default")
      (node (ref "U51") (pin "53") (pinfunction "3.3V_(250_M_A_MAX)_53") (pintype "bidirectional"))
    )
    (net (code "82") (name "unconnected-(U51-A0-Pad14)") (class "Default")
      (node (ref "U51") (pin "14") (pinfunction "A0_14") (pintype "bidirectional"))
    )
    (net (code "83") (name "unconnected-(U51-A1-Pad15)") (class "Default")
      (node (ref "U51") (pin "15") (pinfunction "A1_15") (pintype "bidirectional"))
    )
    (net (code "84") (name "unconnected-(U51-A2-Pad16)") (class "Default")
      (node (ref "U51") (pin "16") (pinfunction "A2_16") (pintype "bidirectional"))
    )
    (net (code "85") (name "unconnected-(U51-A3-Pad17)") (class "Default")
      (node (ref "U51") (pin "17") (pinfunction "A3_17") (pintype "bidirectional"))
    )
    (net (code "86") (name "unconnected-(U51-A4-Pad18)") (class "Default")
      (node (ref "U51") (pin "18") (pinfunction "A4_18") (pintype "bidirectional"))
    )
    (net (code "87") (name "unconnected-(U51-A5-Pad19)") (class "Default")
      (node (ref "U51") (pin "19") (pinfunction "A5_19") (pintype "bidirectional"))
    )
    (net (code "88") (name "unconnected-(U51-A6-Pad20)") (class "Default")
      (node (ref "U51") (pin "20") (pinfunction "A6_20") (pintype "bidirectional"))
    )
    (net (code "89") (name "unconnected-(U51-A7-Pad21)") (class "Default")
      (node (ref "U51") (pin "21") (pinfunction "A7_21") (pintype "bidirectional"))
    )
    (net (code "90") (name "unconnected-(U51-A8-Pad22)") (class "Default")
      (node (ref "U51") (pin "22") (pinfunction "A8_22") (pintype "bidirectional"))
    )
    (net (code "91") (name "unconnected-(U51-A9-Pad23)") (class "Default")
      (node (ref "U51") (pin "23") (pinfunction "A9_23") (pintype "bidirectional"))
    )
    (net (code "92") (name "unconnected-(U51-A10-Pad24)") (class "Default")
      (node (ref "U51") (pin "24") (pinfunction "A10_24") (pintype "bidirectional"))
    )
    (net (code "93") (name "unconnected-(U51-A11-Pad25)") (class "Default")
      (node (ref "U51") (pin "25") (pinfunction "A11_25") (pintype "bidirectional"))
    )
    (net (code "94") (name "unconnected-(U51-A14-Pad38)") (class "Default")
      (node (ref "U51") (pin "38") (pinfunction "A14_38") (pintype "bidirectional"))
    )
    (net (code "95") (name "unconnected-(U51-A16-Pad40)") (class "Default")
      (node (ref "U51") (pin "40") (pinfunction "A16_40") (pintype "bidirectional"))
    )
    (net (code "96") (name "unconnected-(U51-A17-Pad41)") (class "Default")
      (node (ref "U51") (pin "41") (pinfunction "A17_41") (pintype "bidirectional"))
    )
    (net (code "97") (name "unconnected-(U51-BCLK2-Pad4)") (class "Default")
      (node (ref "U51") (pin "4") (pinfunction "BCLK2_4") (pintype "bidirectional"))
    )
    (net (code "98") (name "unconnected-(U51-CRX3-Pad30)") (class "Default")
      (node (ref "U51") (pin "30") (pinfunction "CRX3_30") (pintype "bidirectional"))
    )
    (net (code "99") (name "unconnected-(U51-CS_2-Pad36)") (class "Default")
      (node (ref "U51") (pin "36") (pinfunction "CS_2_36") (pintype "bidirectional"))
    )
    (net (code "100") (name "unconnected-(U51-CS_3-Pad37)") (class "Default")
      (node (ref "U51") (pin "37") (pinfunction "CS_3_37") (pintype "bidirectional"))
    )
    (net (code "101") (name "unconnected-(U51-CTX3-Pad31)") (class "Default")
      (node (ref "U51") (pin "31") (pinfunction "CTX3_31") (pintype "bidirectional"))
    )
    (net (code "102") (name "unconnected-(U51-D+-Pad50)") (class "Default")
      (node (ref "U51") (pin "50") (pinfunction "D+_50") (pintype "bidirectional"))
    )
    (net (code "103") (name "unconnected-(U51-D--Pad51)") (class "Default")
      (node (ref "U51") (pin "51") (pinfunction "D-_51") (pintype "bidirectional"))
    )
    (net (code "104") (name "unconnected-(U51-IN2-Pad5)") (class "Default")
      (node (ref "U51") (pin "5") (pinfunction "IN2_5") (pintype "bidirectional"))
    )
    (net (code "105") (name "unconnected-(U51-LRCLK2-Pad3)") (class "Default")
      (node (ref "U51") (pin "3") (pinfunction "LRCLK2_3") (pintype "bidirectional"))
    )
    (net (code "106") (name "unconnected-(U51-MCLK2-Pad33)") (class "Default")
      (node (ref "U51") (pin "33") (pinfunction "MCLK2_33") (pintype "bidirectional"))
    )
    (net (code "107") (name "unconnected-(U51-ON{slash}OFF-Pad47)") (class "Default")
      (node (ref "U51") (pin "47") (pinfunction "ON/OFF_47") (pintype "bidirectional"))
    )
    (net (code "108") (name "unconnected-(U51-OUT1B-Pad32)") (class "Default")
      (node (ref "U51") (pin "32") (pinfunction "OUT1B_32") (pintype "bidirectional"))
    )
    (net (code "109") (name "unconnected-(U51-OUT1C-Pad9)") (class "Default")
      (node (ref "U51") (pin "9") (pinfunction "OUT1C_9") (pintype "bidirectional"))
    )
    (net (code "110") (name "unconnected-(U51-OUT1D-Pad6)") (class "Default")
      (node (ref "U51") (pin "6") (pinfunction "OUT1D_6") (pintype "bidirectional"))
    )
    (net (code "111") (name "unconnected-(U51-OUT2-Pad2)") (class "Default")
      (node (ref "U51") (pin "2") (pinfunction "OUT2_2") (pintype "bidirectional"))
    )
    (net (code "112") (name "unconnected-(U51-PROGRAM-Pad46)") (class "Default")
      (node (ref "U51") (pin "46") (pinfunction "PROGRAM_46") (pintype "bidirectional"))
    )
    (net (code "113") (name "unconnected-(U51-RX1-Pad57)") (class "Default")
      (node (ref "U51") (pin "57") (pinfunction "RX1_57") (pintype "bidirectional"))
    )
    (net (code "114") (name "unconnected-(U51-RX2-Pad7)") (class "Default")
      (node (ref "U51") (pin "7") (pinfunction "RX2_7") (pintype "bidirectional"))
    )
    (net (code "115") (name "unconnected-(U51-RX8-Pad34)") (class "Default")
      (node (ref "U51") (pin "34") (pinfunction "RX8_34") (pintype "bidirectional"))
    )
    (net (code "116") (name "unconnected-(U51-TX1-Pad1)") (class "Default")
      (node (ref "U51") (pin "1") (pinfunction "TX1_1") (pintype "bidirectional"))
    )
    (net (code "117") (name "unconnected-(U51-TX2-Pad8)") (class "Default")
      (node (ref "U51") (pin "8") (pinfunction "TX2_8") (pintype "bidirectional"))
    )
    (net (code "118") (name "unconnected-(U51-TX7-Pad29)") (class "Default")
      (node (ref "U51") (pin "29") (pinfunction "TX7_29") (pintype "bidirectional"))
    )
    (net (code "119") (name "unconnected-(U51-TX8-Pad35)") (class "Default")
      (node (ref "U51") (pin "35") (pinfunction "TX8_35") (pintype "bidirectional"))
    )
    (net (code "120") (name "unconnected-(U51-VBAT-Pad43)") (class "Default")
      (node (ref "U51") (pin "43") (pinfunction "VBAT_43") (pintype "bidirectional"))
    )
    (net (code "121") (name "unconnected-(U51-VUSB-Pad68)") (class "Default")
      (node (ref "U51") (pin "68") (pinfunction "VUSB_68") (pintype "bidirectional"))
    )
  )
)
